# untitled.net
KiCad netlist of a schematic drawn in EAGLE
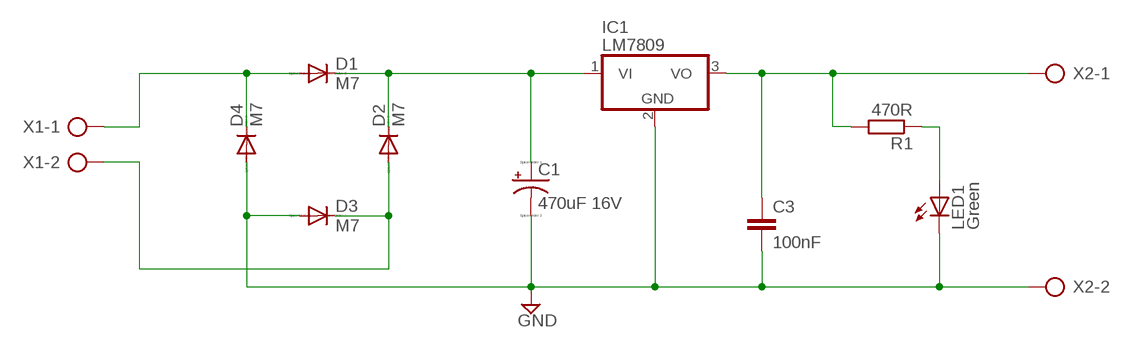
[diagram p0: schematic, sheet 1]

(export (version "E")
  (design (tool "Eeschema 10.0.6"))
  (components
    (comp (ref "C1")
      (value "470uF 16V")
      (footprint "eagle-import:E2,5-6")
      (libsource (lib "eagle-import") (part "CPOL-USE2.5-6"))
    )
    (comp (ref "C3")
      (value "100nF")
      (footprint "eagle-import:C0805")
      (libsource (lib "eagle-import") (part "C-EUC0805"))
    )
    (comp (ref "D1")
      (value "M7")
      (footprint "eagle-import:SOD-123_MINI-SMA")
      (libsource (lib "eagle-import") (part "CGRM400-G3"))
    )
    (comp (ref "D2")
      (value "M7")
      (footprint "eagle-import:SOD-123_MINI-SMA")
      (libsource (lib "eagle-import") (part "CGRM400-G3"))
    )
    (comp (ref "D3")
      (value "M7")
      (footprint "eagle-import:SOD-123_MINI-SMA")
      (libsource (lib "eagle-import") (part "CGRM400-G3"))
    )
    (comp (ref "D4")
      (value "M7")
      (footprint "eagle-import:SOD-123_MINI-SMA")
      (libsource (lib "eagle-import") (part "CGRM400-G3"))
    )
    (comp (ref "IC1")
      (value "LM7809")
      (footprint "eagle-import:TO220H")
      (libsource (lib "eagle-import") (part "78T05"))
    )
    (comp (ref "LED1")
      (value "Green")
      (footprint "eagle-import:LED5MM")
      (libsource (lib "eagle-import") (part "LED5MM"))
    )
    (comp (ref "R1")
      (value "470R")
      (footprint "eagle-import:M3516")
      (libsource (lib "eagle-import") (part "R-EU_M3516"))
    )
    (comp (ref "X1")
      (value "AK500/2")
      (footprint "eagle-import:AK500_2")
      (libsource (lib "eagle-import") (part "AK500/2"))
    )
    (comp (ref "X2")
      (value "AK500/2")
      (footprint "eagle-import:AK500_2")
      (libsource (lib "eagle-import") (part "AK500/2"))
    )
  )
  (nets
    (net (code "1") (name "GND") (class "Default")
      (node (ref "C1") (pin "-") (pinfunction "-_-") (pintype "passive"))
      (node (ref "C3") (pin "2") (pinfunction "2_2") (pintype "passive"))
      (node (ref "D3") (pin "A") (pinfunction "A_A") (pintype "passive"))
      (node (ref "D4") (pin "A") (pinfunction "A_A") (pintype "passive"))
      (node (ref "IC1") (pin "2") (pinfunction "GND_2") (pintype "passive"))
      (node (ref "LED1") (pin "K") (pinfunction "C_K") (pintype "passive"))
      (node (ref "X2") (pin "2") (pinfunction "KL_2") (pintype "passive"))
    )
    (net (code "2") (name "Net-(IC1-VI)") (class "Default")
      (node (ref "C1") (pin "+") (pinfunction "+_+") (pintype "passive"))
      (node (ref "D1") (pin "C") (pinfunction "C_C") (pintype "passive"))
      (node (ref "D2") (pin "C") (pinfunction "C_C") (pintype "passive"))
      (node (ref "IC1") (pin "1") (pinfunction "VI_1") (pintype "input"))
    )
    (net (code "3") (name "Net-(IC1-VO)") (class "Default")
      (node (ref "C3") (pin "1") (pinfunction "1_1") (pintype "passive"))
      (node (ref "IC1") (pin "3") (pinfunction "VO_3") (pintype "passive"))
      (node (ref "R1") (pin "2") (pinfunction "2_2") (pintype "passive"))
      (node (ref "X2") (pin "1") (pinfunction "KL_1") (pintype "passive"))
    )
    (net (code "4") (name "Net-(LED1-PadA)") (class "Default")
      (node (ref "LED1") (pin "A") (pinfunction "A_A") (pintype "passive"))
      (node (ref "R1") (pin "1") (pinfunction "1_1") (pintype "passive"))
    )
    (net (code "5") (name "Net-(X1A-KL)") (class "Default")
      (node (ref "D1") (pin "A") (pinfunction "A_A") (pintype "passive"))
      (node (ref "D4") (pin "C") (pinfunction "C_C") (pintype "passive"))
      (node (ref "X1") (pin "1") (pinfunction "KL_1") (pintype "passive"))
    )
    (net (code "6") (name "Net-(X1B-KL)") (class "Default")
      (node (ref "D2") (pin "A") (pinfunction "A_A") (pintype "passive"))
      (node (ref "D3") (pin "C") (pinfunction "C_C") (pintype "passive"))
      (node (ref "X1") (pin "2") (pinfunction "KL_2") (pintype "passive"))
    )
  )
)
